# STM32F446RC_single_layer_V1.net
KiCad netlist of a schematic drawn in EAGLE
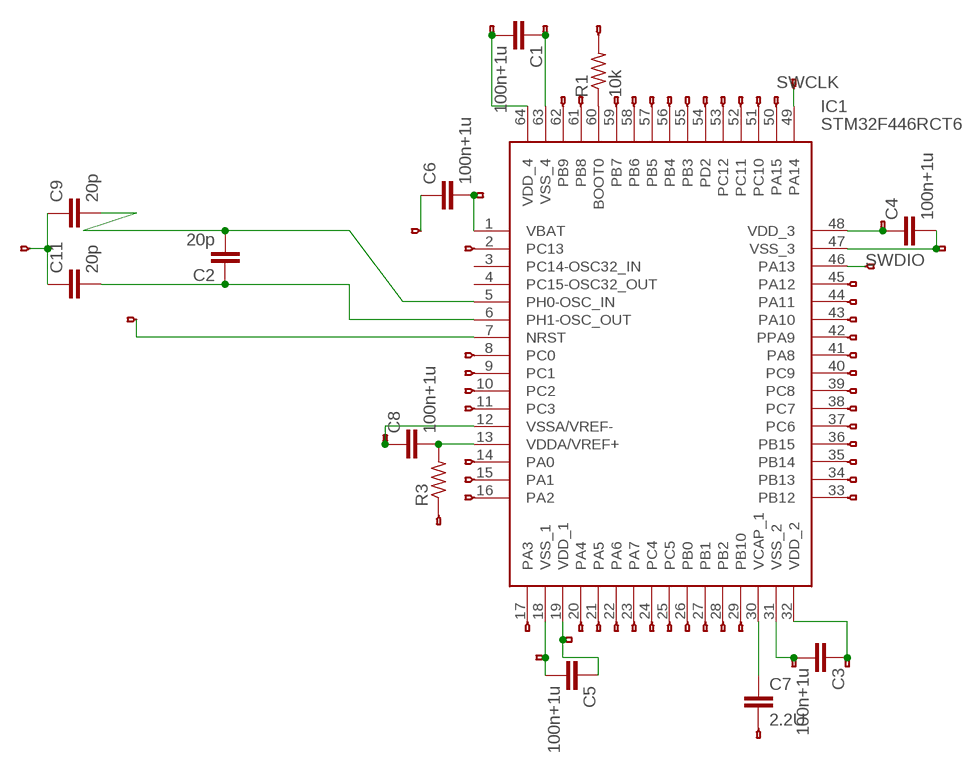
[diagram p0: schematic, sheet 1]

(export (version "E")
  (design (tool "Eeschema 10.0.6"))
  (components
    (comp (ref "C0")
      (value "HEADERHOLE-HEADERHOLE")
      (footprint "eagle-import:1X1-HEADER-HOLE")
      (libsource (lib "eagle-import") (part "HEADERHOLE-HEADERHOLE"))
    )
    (comp (ref "C1")
      (value "100n+1u")
      (footprint "eagle-import:C2.5-3")
      (libsource (lib "eagle-import") (part "C2,5-3"))
    )
    (comp (ref "C2")
      (value "20p")
      (footprint "eagle-import:C2.5-3")
      (libsource (lib "eagle-import") (part "C2,5-3"))
    )
    (comp (ref "C3")
      (value "100n+1u")
      (footprint "eagle-import:C2.5-3")
      (libsource (lib "eagle-import") (part "C2,5-3"))
    )
    (comp (ref "C4")
      (value "100n+1u")
      (footprint "eagle-import:C2.5-3")
      (libsource (lib "eagle-import") (part "C2,5-3"))
    )
    (comp (ref "C5")
      (value "100n+1u")
      (footprint "eagle-import:C2.5-3")
      (libsource (lib "eagle-import") (part "C2,5-3"))
    )
    (comp (ref "C6")
      (value "100n+1u")
      (footprint "eagle-import:C2.5-3")
      (libsource (lib "eagle-import") (part "C2,5-3"))
    )
    (comp (ref "C7")
      (value "2.2U")
      (footprint "eagle-import:C2.5-3")
      (libsource (lib "eagle-import") (part "C2,5-3"))
    )
    (comp (ref "C8")
      (value "100n+1u")
      (footprint "eagle-import:C2.5-3")
      (libsource (lib "eagle-import") (part "C2,5-3"))
    )
    (comp (ref "C9")
      (value "20p")
      (footprint "eagle-import:C2.5-3")
      (libsource (lib "eagle-import") (part "C2,5-3"))
    )
    (comp (ref "C11")
      (value "20p")
      (footprint "eagle-import:C2.5-3")
      (libsource (lib "eagle-import") (part "C2,5-3"))
    )
    (comp (ref "C13")
      (value "HEADERHOLE-HEADERHOLE")
      (footprint "eagle-import:1X1-HEADER-HOLE")
      (libsource (lib "eagle-import") (part "HEADERHOLE-HEADERHOLE"))
    )
    (comp (ref "IC1")
      (value "STM32F446RCT6")
      (footprint "eagle-import:QFP50P1200X1200X160-64N")
      (fields (field (name "MOUSER_PART_NUMBER") "511-STM32F446RCT6"))
      (libsource (lib "eagle-import") (part "STM32F446RCT6"))
    )
    (comp (ref "JP1")
      (value "HEADERHOLE-HEADERHOLE")
      (footprint "eagle-import:1X1-HEADER-HOLE")
      (libsource (lib "eagle-import") (part "HEADERHOLE-HEADERHOLE"))
    )
    (comp (ref "JP2")
      (value "HEADERHOLE-HEADERHOLE")
      (footprint "eagle-import:1X1-HEADER-HOLE")
      (libsource (lib "eagle-import") (part "HEADERHOLE-HEADERHOLE"))
    )
    (comp (ref "JP3")
      (value "HEADERHOLE-HEADERHOLE")
      (footprint "eagle-import:1X1-HEADER-HOLE")
      (libsource (lib "eagle-import") (part "HEADERHOLE-HEADERHOLE"))
    )
    (comp (ref "JP4")
      (value "HEADERHOLE-HEADERHOLE")
      (footprint "eagle-import:1X1-HEADER-HOLE")
      (fields (field (name "SPICEPREFIX") "X"))
      (libsource (lib "eagle-import") (part "HEADERHOLE-HEADERHOLE"))
    )
    (comp (ref "JP5")
      (value "HEADERHOLE-HEADERHOLE")
      (footprint "eagle-import:1X1-HEADER-HOLE")
      (libsource (lib "eagle-import") (part "HEADERHOLE-HEADERHOLE"))
    )
    (comp (ref "JP6")
      (value "HEADERHOLE-HEADERHOLE")
      (footprint "eagle-import:1X1-HEADER-HOLE")
      (libsource (lib "eagle-import") (part "HEADERHOLE-HEADERHOLE"))
    )
    (comp (ref "JP7")
      (value "HEADERHOLE-HEADERHOLE")
      (footprint "eagle-import:1X1-HEADER-HOLE")
      (libsource (lib "eagle-import") (part "HEADERHOLE-HEADERHOLE"))
    )
    (comp (ref "JP9")
      (value "HEADERHOLE-HEADERHOLE")
      (footprint "eagle-import:1X1-HEADER-HOLE")
      (libsource (lib "eagle-import") (part "HEADERHOLE-HEADERHOLE"))
    )
    (comp (ref "JP10")
      (value "HEADERHOLE-HEADERHOLE")
      (footprint "eagle-import:1X1-HEADER-HOLE")
      (libsource (lib "eagle-import") (part "HEADERHOLE-HEADERHOLE"))
    )
    (comp (ref "JP11")
      (value "HEADERHOLE-HEADERHOLE")
      (footprint "eagle-import:1X1-HEADER-HOLE")
      (libsource (lib "eagle-import") (part "HEADERHOLE-HEADERHOLE"))
    )
    (comp (ref "JP12")
      (value "HEADERHOLE-HEADERHOLE")
      (footprint "eagle-import:1X1-HEADER-HOLE")
      (libsource (lib "eagle-import") (part "HEADERHOLE-HEADERHOLE"))
    )
    (comp (ref "JP13")
      (value "HEADERHOLE-HEADERHOLE")
      (footprint "eagle-import:1X1-HEADER-HOLE")
      (libsource (lib "eagle-import") (part "HEADERHOLE-HEADERHOLE"))
    )
    (comp (ref "JP14")
      (value "HEADERHOLE-HEADERHOLE")
      (footprint "eagle-import:1X1-HEADER-HOLE")
      (libsource (lib "eagle-import") (part "HEADERHOLE-HEADERHOLE"))
    )
    (comp (ref "JP15")
      (value "HEADERHOLE-HEADERHOLE")
      (footprint "eagle-import:1X1-HEADER-HOLE")
      (libsource (lib "eagle-import") (part "HEADERHOLE-HEADERHOLE"))
    )
    (comp (ref "JP16")
      (value "HEADERHOLE-HEADERHOLE")
      (footprint "eagle-import:1X1-HEADER-HOLE")
      (libsource (lib "eagle-import") (part "HEADERHOLE-HEADERHOLE"))
    )
    (comp (ref "JP17")
      (value "HEADERHOLE-HEADERHOLE")
      (footprint "eagle-import:1X1-HEADER-HOLE")
      (libsource (lib "eagle-import") (part "HEADERHOLE-HEADERHOLE"))
    )
    (comp (ref "JP18")
      (value "HEADERHOLE-HEADERHOLE")
      (footprint "eagle-import:1X1-HEADER-HOLE")
      (libsource (lib "eagle-import") (part "HEADERHOLE-HEADERHOLE"))
    )
    (comp (ref "JP19")
      (value "HEADERHOLE-HEADERHOLE")
      (footprint "eagle-import:1X1-HEADER-HOLE")
      (libsource (lib "eagle-import") (part "HEADERHOLE-HEADERHOLE"))
    )
    (comp (ref "JP20")
      (value "HEADERHOLE-HEADERHOLE")
      (footprint "eagle-import:1X1-HEADER-HOLE")
      (libsource (lib "eagle-import") (part "HEADERHOLE-HEADERHOLE"))
    )
    (comp (ref "JP21")
      (value "HEADERHOLE-HEADERHOLE")
      (footprint "eagle-import:1X1-HEADER-HOLE")
      (libsource (lib "eagle-import") (part "HEADERHOLE-HEADERHOLE"))
    )
    (comp (ref "JP22")
      (value "HEADERHOLE-HEADERHOLE")
      (footprint "eagle-import:1X1-HEADER-HOLE")
      (libsource (lib "eagle-import") (part "HEADERHOLE-HEADERHOLE"))
    )
    (comp (ref "JP23")
      (value "HEADERHOLE-HEADERHOLE")
      (footprint "eagle-import:1X1-HEADER-HOLE")
      (libsource (lib "eagle-import") (part "HEADERHOLE-HEADERHOLE"))
    )
    (comp (ref "JP24")
      (value "HEADERHOLE-HEADERHOLE")
      (footprint "eagle-import:1X1-HEADER-HOLE")
      (libsource (lib "eagle-import") (part "HEADERHOLE-HEADERHOLE"))
    )
    (comp (ref "JP25")
      (value "HEADERHOLE-HEADERHOLE")
      (footprint "eagle-import:1X1-HEADER-HOLE")
      (libsource (lib "eagle-import") (part "HEADERHOLE-HEADERHOLE"))
    )
    (comp (ref "JP27")
      (value "HEADERHOLE-HEADERHOLE")
      (footprint "eagle-import:1X1-HEADER-HOLE")
      (libsource (lib "eagle-import") (part "HEADERHOLE-HEADERHOLE"))
    )
    (comp (ref "JP28")
      (value "HEADERHOLE-HEADERHOLE")
      (footprint "eagle-import:1X1-HEADER-HOLE")
      (libsource (lib "eagle-import") (part "HEADERHOLE-HEADERHOLE"))
    )
    (comp (ref "JP30")
      (value "HEADERHOLE-HEADERHOLE")
      (footprint "eagle-import:1X1-HEADER-HOLE")
      (libsource (lib "eagle-import") (part "HEADERHOLE-HEADERHOLE"))
    )
    (comp (ref "JP31")
      (value "HEADERHOLE-HEADERHOLE")
      (footprint "eagle-import:1X1-HEADER-HOLE")
      (libsource (lib "eagle-import") (part "HEADERHOLE-HEADERHOLE"))
    )
    (comp (ref "JP32")
      (value "HEADERHOLE-HEADERHOLE")
      (footprint "eagle-import:1X1-HEADER-HOLE")
      (libsource (lib "eagle-import") (part "HEADERHOLE-HEADERHOLE"))
    )
    (comp (ref "JP33")
      (value "HEADERHOLE-HEADERHOLE")
      (footprint "eagle-import:1X1-HEADER-HOLE")
      (libsource (lib "eagle-import") (part "HEADERHOLE-HEADERHOLE"))
    )
    (comp (ref "JP34")
      (value "HEADERHOLE-HEADERHOLE")
      (footprint "eagle-import:1X1-HEADER-HOLE")
      (libsource (lib "eagle-import") (part "HEADERHOLE-HEADERHOLE"))
    )
    (comp (ref "JP35")
      (value "HEADERHOLE-HEADERHOLE")
      (footprint "eagle-import:1X1-HEADER-HOLE")
      (libsource (lib "eagle-import") (part "HEADERHOLE-HEADERHOLE"))
    )
    (comp (ref "JP36")
      (value "HEADERHOLE-HEADERHOLE")
      (footprint "eagle-import:1X1-HEADER-HOLE")
      (libsource (lib "eagle-import") (part "HEADERHOLE-HEADERHOLE"))
    )
    (comp (ref "JP37")
      (value "HEADERHOLE-HEADERHOLE")
      (footprint "eagle-import:1X1-HEADER-HOLE")
      (libsource (lib "eagle-import") (part "HEADERHOLE-HEADERHOLE"))
    )
    (comp (ref "JP38")
      (value "HEADERHOLE-HEADERHOLE")
      (footprint "eagle-import:1X1-HEADER-HOLE")
      (libsource (lib "eagle-import") (part "HEADERHOLE-HEADERHOLE"))
    )
    (comp (ref "JP39")
      (value "HEADERHOLE-HEADERHOLE")
      (footprint "eagle-import:1X1-HEADER-HOLE")
      (libsource (lib "eagle-import") (part "HEADERHOLE-HEADERHOLE"))
    )
    (comp (ref "JP40")
      (value "HEADERHOLE-HEADERHOLE")
      (footprint "eagle-import:1X1-HEADER-HOLE")
      (libsource (lib "eagle-import") (part "HEADERHOLE-HEADERHOLE"))
    )
    (comp (ref "JP41")
      (value "HEADERHOLE-HEADERHOLE")
      (footprint "eagle-import:1X1-HEADER-HOLE")
      (libsource (lib "eagle-import") (part "HEADERHOLE-HEADERHOLE"))
    )
    (comp (ref "JP42")
      (value "HEADERHOLE-HEADERHOLE")
      (footprint "eagle-import:1X1-HEADER-HOLE")
      (libsource (lib "eagle-import") (part "HEADERHOLE-HEADERHOLE"))
    )
    (comp (ref "JP43")
      (value "HEADERHOLE-HEADERHOLE")
      (footprint "eagle-import:1X1-HEADER-HOLE")
      (libsource (lib "eagle-import") (part "HEADERHOLE-HEADERHOLE"))
    )
    (comp (ref "JP44")
      (value "HEADERHOLE-HEADERHOLE")
      (footprint "eagle-import:1X1-HEADER-HOLE")
      (libsource (lib "eagle-import") (part "HEADERHOLE-HEADERHOLE"))
    )
    (comp (ref "JP45")
      (value "HEADERHOLE-HEADERHOLE")
      (footprint "eagle-import:1X1-HEADER-HOLE")
      (libsource (lib "eagle-import") (part "HEADERHOLE-HEADERHOLE"))
    )
    (comp (ref "JP46")
      (value "HEADERHOLE-HEADERHOLE")
      (footprint "eagle-import:1X1-HEADER-HOLE")
      (libsource (lib "eagle-import") (part "HEADERHOLE-HEADERHOLE"))
    )
    (comp (ref "JP47")
      (value "HEADERHOLE-HEADERHOLE")
      (footprint "eagle-import:1X1-HEADER-HOLE")
      (libsource (lib "eagle-import") (part "HEADERHOLE-HEADERHOLE"))
    )
    (comp (ref "JP48")
      (value "HEADERHOLE-HEADERHOLE")
      (footprint "eagle-import:1X1-HEADER-HOLE")
      (libsource (lib "eagle-import") (part "HEADERHOLE-HEADERHOLE"))
    )
    (comp (ref "JP49")
      (value "HEADERHOLE-HEADERHOLE")
      (footprint "eagle-import:1X1-HEADER-HOLE")
      (libsource (lib "eagle-import") (part "HEADERHOLE-HEADERHOLE"))
    )
    (comp (ref "JP50")
      (value "HEADERHOLE-HEADERHOLE")
      (footprint "eagle-import:1X1-HEADER-HOLE")
      (libsource (lib "eagle-import") (part "HEADERHOLE-HEADERHOLE"))
    )
    (comp (ref "JP51")
      (value "HEADERHOLE-HEADERHOLE")
      (footprint "eagle-import:1X1-HEADER-HOLE")
      (libsource (lib "eagle-import") (part "HEADERHOLE-HEADERHOLE"))
    )
    (comp (ref "JP52")
      (value "HEADERHOLE-HEADERHOLE")
      (footprint "eagle-import:1X1-HEADER-HOLE")
      (libsource (lib "eagle-import") (part "HEADERHOLE-HEADERHOLE"))
    )
    (comp (ref "JP53")
      (value "HEADERHOLE-HEADERHOLE")
      (footprint "eagle-import:1X1-HEADER-HOLE")
      (libsource (lib "eagle-import") (part "HEADERHOLE-HEADERHOLE"))
    )
    (comp (ref "JP54")
      (value "HEADERHOLE-HEADERHOLE")
      (footprint "eagle-import:1X1-HEADER-HOLE")
      (libsource (lib "eagle-import") (part "HEADERHOLE-HEADERHOLE"))
    )
    (comp (ref "JP55")
      (value "HEADERHOLE-HEADERHOLE")
      (footprint "eagle-import:1X1-HEADER-HOLE")
      (libsource (lib "eagle-import") (part "HEADERHOLE-HEADERHOLE"))
    )
    (comp (ref "JP56")
      (value "HEADERHOLE-HEADERHOLE")
      (footprint "eagle-import:1X1-HEADER-HOLE")
      (libsource (lib "eagle-import") (part "HEADERHOLE-HEADERHOLE"))
    )
    (comp (ref "JP57")
      (value "HEADERHOLE-HEADERHOLE")
      (footprint "eagle-import:1X1-HEADER-HOLE")
      (libsource (lib "eagle-import") (part "HEADERHOLE-HEADERHOLE"))
    )
    (comp (ref "JP58")
      (value "HEADERHOLE-HEADERHOLE")
      (footprint "eagle-import:1X1-HEADER-HOLE")
      (libsource (lib "eagle-import") (part "HEADERHOLE-HEADERHOLE"))
    )
    (comp (ref "JP59")
      (value "HEADERHOLE-HEADERHOLE")
      (footprint "eagle-import:1X1-HEADER-HOLE")
      (libsource (lib "eagle-import") (part "HEADERHOLE-HEADERHOLE"))
    )
    (comp (ref "JP61")
      (value "HEADERHOLE-HEADERHOLE")
      (footprint "eagle-import:1X1-HEADER-HOLE")
      (libsource (lib "eagle-import") (part "HEADERHOLE-HEADERHOLE"))
    )
    (comp (ref "JP62")
      (value "HEADERHOLE-HEADERHOLE")
      (footprint "eagle-import:1X1-HEADER-HOLE")
      (libsource (lib "eagle-import") (part "HEADERHOLE-HEADERHOLE"))
    )
    (comp (ref "JP63")
      (value "HEADERHOLE-HEADERHOLE")
      (footprint "eagle-import:1X1-HEADER-HOLE")
      (libsource (lib "eagle-import") (part "HEADERHOLE-HEADERHOLE"))
    )
    (comp (ref "JP65")
      (value "HEADERHOLE-HEADERHOLE")
      (footprint "eagle-import:1X1-HEADER-HOLE")
      (libsource (lib "eagle-import") (part "HEADERHOLE-HEADERHOLE"))
    )
    (comp (ref "R1")
      (value "10k")
      (footprint "eagle-import:0204V")
      (libsource (lib "eagle-import") (part "R-US_0204/2V"))
    )
    (comp (ref "R3")
      (value "R-US_0204/2V")
      (footprint "eagle-import:0204V")
      (libsource (lib "eagle-import") (part "R-US_0204/2V"))
    )
  )
  (nets
    (net (code "1") (name "/SWCLK") (class "Default")
      (node (ref "IC1") (pin "49") (pinfunction "PA14_49") (pintype "bidirectional"))
      (node (ref "JP55") (pin "1") (pinfunction "P$1_1") (pintype "bidirectional"))
    )
    (net (code "2") (name "/SWDIO") (class "Default")
      (node (ref "IC1") (pin "46") (pinfunction "PA13_46") (pintype "bidirectional"))
      (node (ref "JP54") (pin "1") (pinfunction "P$1_1") (pintype "bidirectional"))
    )
    (net (code "3") (name "Net-(C0-P$1)") (class "Default")
      (node (ref "C0") (pin "1") (pinfunction "P$1_1") (pintype "bidirectional"))
      (node (ref "IC1") (pin "8") (pinfunction "PC0_8") (pintype "bidirectional"))
    )
    (net (code "4") (name "Net-(C13-P$1)") (class "Default")
      (node (ref "C13") (pin "1") (pinfunction "P$1_1") (pintype "bidirectional"))
      (node (ref "IC1") (pin "2") (pinfunction "PC13_2") (pintype "bidirectional"))
    )
    (net (code "5") (name "Net-(IC1-BOOT0)") (class "Default")
      (node (ref "IC1") (pin "60") (pinfunction "BOOT0_60") (pintype "bidirectional"))
      (node (ref "R1") (pin "1") (pinfunction "1_1") (pintype "passive"))
    )
    (net (code "6") (name "Net-(IC1-NRST)") (class "Default")
      (node (ref "IC1") (pin "7") (pinfunction "NRST_7") (pintype "bidirectional"))
      (node (ref "JP63") (pin "1") (pinfunction "P$1_1") (pintype "bidirectional"))
    )
    (net (code "7") (name "Net-(IC1-PA0)") (class "Default")
      (node (ref "IC1") (pin "14") (pinfunction "PA0_14") (pintype "bidirectional"))
      (node (ref "JP34") (pin "1") (pinfunction "P$1_1") (pintype "bidirectional"))
    )
    (net (code "8") (name "Net-(IC1-PA1)") (class "Default")
      (node (ref "IC1") (pin "15") (pinfunction "PA1_15") (pintype "bidirectional"))
      (node (ref "JP35") (pin "1") (pinfunction "P$1_1") (pintype "bidirectional"))
    )
    (net (code "9") (name "Net-(IC1-PA2)") (class "Default")
      (node (ref "IC1") (pin "16") (pinfunction "PA2_16") (pintype "bidirectional"))
      (node (ref "JP36") (pin "1") (pinfunction "P$1_1") (pintype "bidirectional"))
    )
    (net (code "10") (name "Net-(IC1-PA3)") (class "Default")
      (node (ref "IC1") (pin "17") (pinfunction "PA3_17") (pintype "bidirectional"))
      (node (ref "JP24") (pin "1") (pinfunction "P$1_1") (pintype "bidirectional"))
    )
    (net (code "11") (name "Net-(IC1-PA4)") (class "Default")
      (node (ref "IC1") (pin "20") (pinfunction "PA4_20") (pintype "bidirectional"))
      (node (ref "JP21") (pin "1") (pinfunction "P$1_1") (pintype "bidirectional"))
    )
    (net (code "12") (name "Net-(IC1-PA5)") (class "Default")
      (node (ref "IC1") (pin "21") (pinfunction "PA5_21") (pintype "bidirectional"))
      (node (ref "JP19") (pin "1") (pinfunction "P$1_1") (pintype "bidirectional"))
    )
    (net (code "13") (name "Net-(IC1-PA6)") (class "Default")
      (node (ref "IC1") (pin "22") (pinfunction "PA6_22") (pintype "bidirectional"))
      (node (ref "JP9") (pin "1") (pinfunction "P$1_1") (pintype "bidirectional"))
    )
    (net (code "14") (name "Net-(IC1-PA7)") (class "Default")
      (node (ref "IC1") (pin "23") (pinfunction "PA7_23") (pintype "bidirectional"))
      (node (ref "JP11") (pin "1") (pinfunction "P$1_1") (pintype "bidirectional"))
    )
    (net (code "15") (name "Net-(IC1-PA8)") (class "Default")
      (node (ref "IC1") (pin "41") (pinfunction "PA8_41") (pintype "bidirectional"))
      (node (ref "JP28") (pin "1") (pinfunction "P$1_1") (pintype "bidirectional"))
    )
    (net (code "16") (name "Net-(IC1-PA10)") (class "Default")
      (node (ref "IC1") (pin "43") (pinfunction "PA10_43") (pintype "bidirectional"))
      (node (ref "JP33") (pin "1") (pinfunction "P$1_1") (pintype "bidirectional"))
    )
    (net (code "17") (name "Net-(IC1-PA11)") (class "Default")
      (node (ref "IC1") (pin "44") (pinfunction "PA11_44") (pintype "bidirectional"))
      (node (ref "JP32") (pin "1") (pinfunction "P$1_1") (pintype "bidirectional"))
    )
    (net (code "18") (name "Net-(IC1-PA12)") (class "Default")
      (node (ref "IC1") (pin "45") (pinfunction "PA12_45") (pintype "bidirectional"))
      (node (ref "JP25") (pin "1") (pinfunction "P$1_1") (pintype "bidirectional"))
    )
    (net (code "19") (name "Net-(IC1-PA15)") (class "Default")
      (node (ref "IC1") (pin "50") (pinfunction "PA15_50") (pintype "bidirectional"))
      (node (ref "JP45") (pin "1") (pinfunction "P$1_1") (pintype "bidirectional"))
    )
    (net (code "20") (name "Net-(IC1-PB0)") (class "Default")
      (node (ref "IC1") (pin "26") (pinfunction "PB0_26") (pintype "bidirectional"))
      (node (ref "JP22") (pin "1") (pinfunction "P$1_1") (pintype "bidirectional"))
    )
    (net (code "21") (name "Net-(IC1-PB1)") (class "Default")
      (node (ref "IC1") (pin "27") (pinfunction "PB1_27") (pintype "bidirectional"))
      (node (ref "JP17") (pin "1") (pinfunction "P$1_1") (pintype "bidirectional"))
    )
    (net (code "22") (name "Net-(IC1-PB2)") (class "Default")
      (node (ref "IC1") (pin "28") (pinfunction "PB2_28") (pintype "bidirectional"))
      (node (ref "JP16") (pin "1") (pinfunction "P$1_1") (pintype "bidirectional"))
    )
    (net (code "23") (name "Net-(IC1-PB3)") (class "Default")
      (node (ref "IC1") (pin "55") (pinfunction "PB3_55") (pintype "bidirectional"))
      (node (ref "JP44") (pin "1") (pinfunction "P$1_1") (pintype "bidirectional"))
    )
    (net (code "24") (name "Net-(IC1-PB4)") (class "Default")
      (node (ref "IC1") (pin "56") (pinfunction "PB4_56") (pintype "bidirectional"))
      (node (ref "JP40") (pin "1") (pinfunction "P$1_1") (pintype "bidirectional"))
    )
    (net (code "25") (name "Net-(IC1-PB5)") (class "Default")
      (node (ref "IC1") (pin "57") (pinfunction "PB5_57") (pintype "bidirectional"))
      (node (ref "JP41") (pin "1") (pinfunction "P$1_1") (pintype "bidirectional"))
    )
    (net (code "26") (name "Net-(IC1-PB6)") (class "Default")
      (node (ref "IC1") (pin "58") (pinfunction "PB6_58") (pintype "bidirectional"))
      (node (ref "JP42") (pin "1") (pinfunction "P$1_1") (pintype "bidirectional"))
    )
    (net (code "27") (name "Net-(IC1-PB7)") (class "Default")
      (node (ref "IC1") (pin "59") (pinfunction "PB7_59") (pintype "bidirectional"))
      (node (ref "JP43") (pin "1") (pinfunction "P$1_1") (pintype "bidirectional"))
    )
    (net (code "28") (name "Net-(IC1-PB8)") (class "Default")
      (node (ref "IC1") (pin "61") (pinfunction "PB8_61") (pintype "bidirectional"))
      (node (ref "JP46") (pin "1") (pinfunction "P$1_1") (pintype "bidirectional"))
    )
    (net (code "29") (name "Net-(IC1-PB9)") (class "Default")
      (node (ref "IC1") (pin "62") (pinfunction "PB9_62") (pintype "bidirectional"))
      (node (ref "JP47") (pin "1") (pinfunction "P$1_1") (pintype "bidirectional"))
    )
    (net (code "30") (name "Net-(IC1-PB10)") (class "Default")
      (node (ref "IC1") (pin "29") (pinfunction "PB10_29") (pintype "bidirectional"))
      (node (ref "JP14") (pin "1") (pinfunction "P$1_1") (pintype "bidirectional"))
    )
    (net (code "31") (name "Net-(IC1-PB12)") (class "Default")
      (node (ref "IC1") (pin "33") (pinfunction "PB12_33") (pintype "bidirectional"))
      (node (ref "JP18") (pin "1") (pinfunction "P$1_1") (pintype "bidirectional"))
    )
    (net (code "32") (name "Net-(IC1-PB13)") (class "Default")
      (node (ref "IC1") (pin "34") (pinfunction "PB13_34") (pintype "bidirectional"))
      (node (ref "JP13") (pin "1") (pinfunction "P$1_1") (pintype "bidirectional"))
    )
    (net (code "33") (name "Net-(IC1-PB14)") (class "Default")
      (node (ref "IC1") (pin "35") (pinfunction "PB14_35") (pintype "bidirectional"))
      (node (ref "JP6") (pin "1") (pinfunction "P$1_1") (pintype "bidirectional"))
    )
    (net (code "34") (name "Net-(IC1-PB15)") (class "Default")
      (node (ref "IC1") (pin "36") (pinfunction "PB15_36") (pintype "bidirectional"))
      (node (ref "JP10") (pin "1") (pinfunction "P$1_1") (pintype "bidirectional"))
    )
    (net (code "35") (name "Net-(IC1-PC1)") (class "Default")
      (node (ref "IC1") (pin "9") (pinfunction "PC1_9") (pintype "bidirectional"))
      (node (ref "JP27") (pin "1") (pinfunction "P$1_1") (pintype "bidirectional"))
    )
    (net (code "36") (name "Net-(IC1-PC2)") (class "Default")
      (node (ref "IC1") (pin "10") (pinfunction "PC2_10") (pintype "bidirectional"))
      (node (ref "JP3") (pin "1") (pinfunction "P$1_1") (pintype "bidirectional"))
    )
    (net (code "37") (name "Net-(IC1-PC3)") (class "Default")
      (node (ref "IC1") (pin "11") (pinfunction "PC3_11") (pintype "bidirectional"))
      (node (ref "JP4") (pin "1") (pinfunction "P$1_1") (pintype "bidirectional"))
    )
    (net (code "38") (name "Net-(IC1-PC4)") (class "Default")
      (node (ref "IC1") (pin "24") (pinfunction "PC4_24") (pintype "bidirectional"))
      (node (ref "JP12") (pin "1") (pinfunction "P$1_1") (pintype "bidirectional"))
    )
    (net (code "39") (name "Net-(IC1-PC5)") (class "Default")
      (node (ref "IC1") (pin "25") (pinfunction "PC5_25") (pintype "bidirectional"))
      (node (ref "JP23") (pin "1") (pinfunction "P$1_1") (pintype "bidirectional"))
    )
    (net (code "40") (name "Net-(IC1-PC6)") (class "Default")
      (node (ref "IC1") (pin "37") (pinfunction "PC6_37") (pintype "bidirectional"))
      (node (ref "JP1") (pin "1") (pinfunction "P$1_1") (pintype "bidirectional"))
    )
    (net (code "41") (name "Net-(IC1-PC7)") (class "Default")
      (node (ref "IC1") (pin "38") (pinfunction "PC7_38") (pintype "bidirectional"))
      (node (ref "JP15") (pin "1") (pinfunction "P$1_1") (pintype "bidirectional"))
    )
    (net (code "42") (name "Net-(IC1-PC8)") (class "Default")
      (node (ref "IC1") (pin "39") (pinfunction "PC8_39") (pintype "bidirectional"))
      (node (ref "JP2") (pin "1") (pinfunction "P$1_1") (pintype "bidirectional"))
    )
    (net (code "43") (name "Net-(IC1-PC9)") (class "Default")
      (node (ref "IC1") (pin "40") (pinfunction "PC9_40") (pintype "bidirectional"))
      (node (ref "JP30") (pin "1") (pinfunction "P$1_1") (pintype "bidirectional"))
    )
    (net (code "44") (name "Net-(IC1-PC10)") (class "Default")
      (node (ref "IC1") (pin "51") (pinfunction "PC10_51") (pintype "bidirectional"))
      (node (ref "JP37") (pin "1") (pinfunction "P$1_1") (pintype "bidirectional"))
    )
    (net (code "45") (name "Net-(IC1-PC11)") (class "Default")
      (node (ref "IC1") (pin "52") (pinfunction "PC11_52") (pintype "bidirectional"))
      (node (ref "JP5") (pin "1") (pinfunction "P$1_1") (pintype "bidirectional"))
    )
    (net (code "46") (name "Net-(IC1-PC12)") (class "Default")
      (node (ref "IC1") (pin "53") (pinfunction "PC12_53") (pintype "bidirectional"))
      (node (ref "JP39") (pin "1") (pinfunction "P$1_1") (pintype "bidirectional"))
    )
    (net (code "47") (name "Net-(IC1-PD2)") (class "Default")
      (node (ref "IC1") (pin "54") (pinfunction "PD2_54") (pintype "bidirectional"))
      (node (ref "JP38") (pin "1") (pinfunction "P$1_1") (pintype "bidirectional"))
    )
    (net (code "48") (name "Net-(IC1-PH0-OSC_IN)") (class "Default")
      (node (ref "C2") (pin "2") (pinfunction "2_2") (pintype "passive"))
      (node (ref "C9") (pin "2") (pinfunction "2_2") (pintype "passive"))
      (node (ref "IC1") (pin "5") (pinfunction "PH0-OSC_IN_5") (pintype "bidirectional"))
    )
    (net (code "49") (name "Net-(IC1-PH1-OSC_OUT)") (class "Default")
      (node (ref "C11") (pin "2") (pinfunction "2_2") (pintype "passive"))
      (node (ref "C2") (pin "1") (pinfunction "1_1") (pintype "passive"))
      (node (ref "IC1") (pin "6") (pinfunction "PH1-OSC_OUT_6") (pintype "bidirectional"))
    )
    (net (code "50") (name "Net-(IC1-PPA9)") (class "Default")
      (node (ref "IC1") (pin "42") (pinfunction "PPA9_42") (pintype "bidirectional"))
      (node (ref "JP31") (pin "1") (pinfunction "P$1_1") (pintype "bidirectional"))
    )
    (net (code "51") (name "Net-(IC1-VBAT)") (class "Default")
      (node (ref "C6") (pin "2") (pinfunction "2_2") (pintype "passive"))
      (node (ref "IC1") (pin "1") (pinfunction "VBAT_1") (pintype "bidirectional"))
      (node (ref "JP7") (pin "1") (pinfunction "P$1_1") (pintype "bidirectional"))
    )
    (net (code "52") (name "Net-(IC1-VCAP_1)") (class "Default")
      (node (ref "C7") (pin "1") (pinfunction "1_1") (pintype "passive"))
      (node (ref "IC1") (pin "30") (pinfunction "VCAP_1_30") (pintype "bidirectional"))
    )
    (net (code "53") (name "Net-(IC1-VDDA{slash}VREF+)") (class "Default")
      (node (ref "C8") (pin "2") (pinfunction "2_2") (pintype "passive"))
      (node (ref "IC1") (pin "13") (pinfunction "VDDA/VREF+_13") (pintype "bidirectional"))
      (node (ref "R3") (pin "2") (pinfunction "2_2") (pintype "passive"))
    )
    (net (code "54") (name "Net-(IC1-VDD_1)") (class "Default")
      (node (ref "C5") (pin "1") (pinfunction "1_1") (pintype "passive"))
      (node (ref "IC1") (pin "19") (pinfunction "VDD_1_19") (pintype "bidirectional"))
      (node (ref "JP48") (pin "1") (pinfunction "P$1_1") (pintype "bidirectional"))
    )
    (net (code "55") (name "Net-(IC1-VDD_2)") (class "Default")
      (node (ref "C3") (pin "1") (pinfunction "1_1") (pintype "passive"))
      (node (ref "IC1") (pin "32") (pinfunction "VDD_2_32") (pintype "bidirectional"))
      (node (ref "JP51") (pin "1") (pinfunction "P$1_1") (pintype "bidirectional"))
    )
    (net (code "56") (name "Net-(IC1-VDD_3)") (class "Default")
      (node (ref "C4") (pin "1") (pinfunction "1_1") (pintype "passive"))
      (node (ref "IC1") (pin "48") (pinfunction "VDD_3_48") (pintype "bidirectional"))
      (node (ref "JP53") (pin "1") (pinfunction "P$1_1") (pintype "bidirectional"))
    )
    (net (code "57") (name "Net-(IC1-VDD_4)") (class "Default")
      (node (ref "C1") (pin "2") (pinfunction "2_2") (pintype "passive"))
      (node (ref "IC1") (pin "64") (pinfunction "VDD_4_64") (pintype "bidirectional"))
      (node (ref "JP58") (pin "1") (pinfunction "P$1_1") (pintype "bidirectional"))
    )
    (net (code "58") (name "Net-(IC1-VSSA{slash}VREF-)") (class "Default")
      (node (ref "C8") (pin "1") (pinfunction "1_1") (pintype "passive"))
      (node (ref "IC1") (pin "12") (pinfunction "VSSA/VREF-_12") (pintype "bidirectional"))
      (node (ref "JP62") (pin "1") (pinfunction "P$1_1") (pintype "bidirectional"))
    )
    (net (code "59") (name "Net-(IC1-VSS_1)") (class "Default")
      (node (ref "C5") (pin "2") (pinfunction "2_2") (pintype "passive"))
      (node (ref "IC1") (pin "18") (pinfunction "VSS_1_18") (pintype "bidirectional"))
      (node (ref "JP20") (pin "1") (pinfunction "P$1_1") (pintype "bidirectional"))
    )
    (net (code "60") (name "Net-(IC1-VSS_2)") (class "Default")
      (node (ref "C3") (pin "2") (pinfunction "2_2") (pintype "passive"))
      (node (ref "IC1") (pin "31") (pinfunction "VSS_2_31") (pintype "bidirectional"))
      (node (ref "JP50") (pin "1") (pinfunction "P$1_1") (pintype "bidirectional"))
    )
    (net (code "61") (name "Net-(IC1-VSS_3)") (class "Default")
      (node (ref "C4") (pin "2") (pinfunction "2_2") (pintype "passive"))
      (node (ref "IC1") (pin "47") (pinfunction "VSS_3_47") (pintype "bidirectional"))
      (node (ref "JP52") (pin "1") (pinfunction "P$1_1") (pintype "bidirectional"))
    )
    (net (code "62") (name "Net-(IC1-VSS_4)") (class "Default")
      (node (ref "C1") (pin "1") (pinfunction "1_1") (pintype "passive"))
      (node (ref "IC1") (pin "63") (pinfunction "VSS_4_63") (pintype "bidirectional"))
      (node (ref "JP57") (pin "1") (pinfunction "P$1_1") (pintype "bidirectional"))
    )
    (net (code "63") (name "Net-(JP49-P$1)") (class "Default")
      (node (ref "C7") (pin "2") (pinfunction "2_2") (pintype "passive"))
      (node (ref "JP49") (pin "1") (pinfunction "P$1_1") (pintype "bidirectional"))
    )
    (net (code "64") (name "Net-(JP56-P$1)") (class "Default")
      (node (ref "JP56") (pin "1") (pinfunction "P$1_1") (pintype "bidirectional"))
      (node (ref "R1") (pin "2") (pinfunction "2_2") (pintype "passive"))
    )
    (net (code "65") (name "Net-(JP59-P$1)") (class "Default")
      (node (ref "C6") (pin "1") (pinfunction "1_1") (pintype "passive"))
      (node (ref "JP59") (pin "1") (pinfunction "P$1_1") (pintype "bidirectional"))
    )
    (net (code "66") (name "Net-(JP61-P$1)") (class "Default")
      (node (ref "JP61") (pin "1") (pinfunction "P$1_1") (pintype "bidirectional"))
      (node (ref "R3") (pin "1") (pinfunction "1_1") (pintype "passive"))
    )
    (net (code "67") (name "Net-(JP65-P$1)") (class "Default")
      (node (ref "C11") (pin "1") (pinfunction "1_1") (pintype "passive"))
      (node (ref "C9") (pin "1") (pinfunction "1_1") (pintype "passive"))
      (node (ref "JP65") (pin "1") (pinfunction "P$1_1") (pintype "bidirectional"))
    )
    (net (code "68") (name "unconnected-(IC1-PC14-OSC32_IN-Pad3)") (class "Default")
      (node (ref "IC1") (pin "3") (pinfunction "PC14-OSC32_IN_3") (pintype "bidirectional"))
    )
    (net (code "69") (name "unconnected-(IC1-PC15-OSC32_OUT-Pad4)") (class "Default")
      (node (ref "IC1") (pin "4") (pinfunction "PC15-OSC32_OUT_4") (pintype "bidirectional"))
    )
  )
)
